# ESP8266.net
KiCad netlist of a schematic drawn in Altium Designer
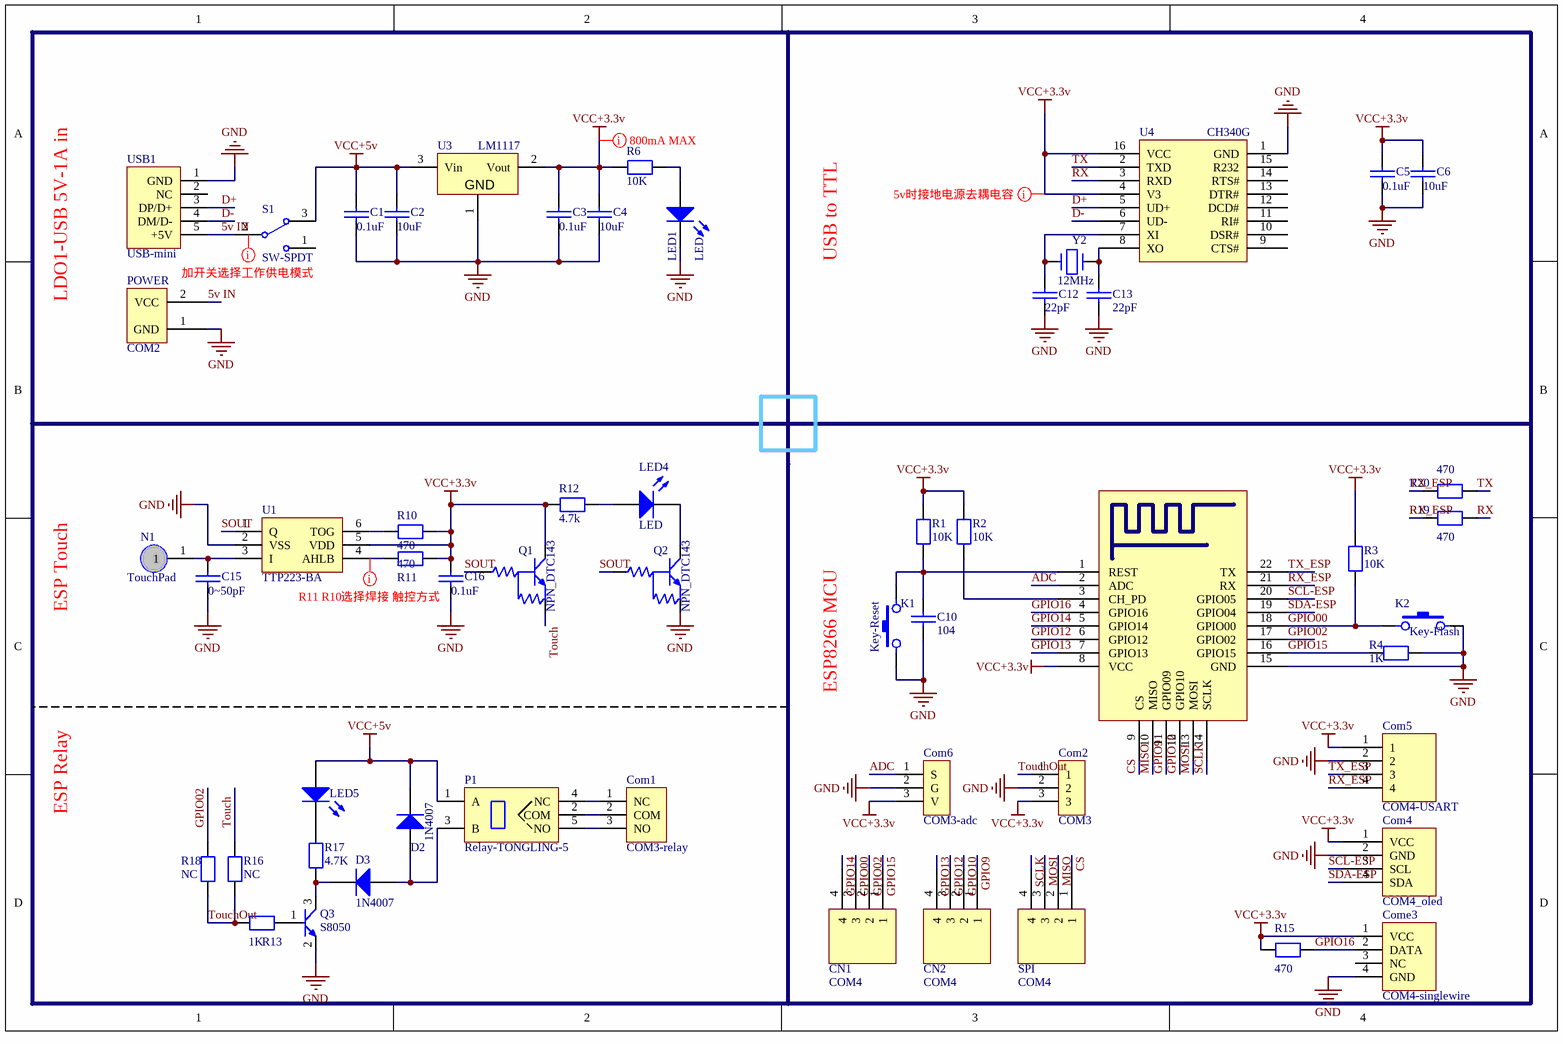
[diagram p0: ESP8266.SchDoc]

(export (version "E")
  (design (tool "Eeschema 10.0.6"))
  (components
    (comp (ref "C1")
      (value "0.1uF")
      (footprint "0603C")
      (description "Capacitor")
      (libsource (lib "myLib") (part "CAP"))
    )
    (comp (ref "C2")
      (value "10uF")
      (footprint "0603C")
      (description "Capacitor")
      (libsource (lib "myLib") (part "CAP"))
    )
    (comp (ref "C3")
      (value "0.1uF")
      (footprint "0603C")
      (description "Capacitor")
      (libsource (lib "myLib") (part "CAP"))
    )
    (comp (ref "C4")
      (value "10uF")
      (footprint "0603C")
      (description "Capacitor")
      (libsource (lib "myLib") (part "CAP"))
    )
    (comp (ref "C5")
      (value "0.1uF")
      (footprint "0603C")
      (description "Capacitor")
      (libsource (lib "myLib") (part "CAP"))
    )
    (comp (ref "C6")
      (value "10uF")
      (footprint "0603C")
      (description "Capacitor")
      (libsource (lib "myLib") (part "CAP"))
    )
    (comp (ref "C10")
      (value "104")
      (footprint "0603C")
      (description "Capacitor")
      (libsource (lib "myLib") (part "CAP"))
    )
    (comp (ref "C12")
      (value "22pF")
      (footprint "0603C")
      (description "Capacitor")
      (libsource (lib "myLib") (part "CAP"))
    )
    (comp (ref "C13")
      (value "22pF")
      (footprint "0603C")
      (description "Capacitor")
      (libsource (lib "myLib") (part "CAP"))
    )
    (comp (ref "C15")
      (value "0~50pF")
      (footprint "0603C")
      (description "Capacitor")
      (libsource (lib "myLib") (part "CAP"))
    )
    (comp (ref "C16")
      (value "0.1uF")
      (footprint "0603C")
      (description "Capacitor")
      (libsource (lib "myLib") (part "CAP"))
    )
    (comp (ref "CN1")
      (value "COM4")
      (footprint "HDR2.54-LI-4P")
      (libsource (lib "altium-import") (part "root_3_COM4_"))
    )
    (comp (ref "CN2")
      (value "COM4")
      (footprint "HDR2.54-LI-4P")
      (libsource (lib "altium-import") (part "root_3_COM4_"))
    )
    (comp (ref "Com1")
      (value "COM3-relay")
      (footprint "KF301-5.0-3P")
      (libsource (lib "myLib") (part "COM3-relay"))
    )
    (comp (ref "Com2") (value "COM3") (footprint "HDR2.54-M-LI-3P") (libsource (lib "myLib") (part "COM3")))
    (comp (ref "Com4")
      (value "COM4_oled")
      (footprint "HDR2.54-4P")
      (libsource (lib "altium-import") (part "root_0_COM4_oled_"))
    )
    (comp (ref "Com5")
      (value "COM4-USART")
      (footprint "HDR2.54-LI-4P")
      (libsource (lib "altium-import") (part "root_0_COM4_"))
    )
    (comp (ref "Com6")
      (value "COM3-adc")
      (footprint "HDR2.54-LI-3P")
      (libsource (lib "myLib") (part "COM3-adc"))
    )
    (comp (ref "Come3")
      (value "COM4-singlewire")
      (footprint "HDR2.54-4P")
      (libsource (lib "myLib") (part "COM4-singlewire"))
    )
    (comp (ref "D2")
      (value "1N4007")
      (footprint "SOD-123")
      (description "High Conductance Fast Diode")
      (fields (field (name "PUBLISHER") "Altium Limited"))
      (libsource (lib "altium-import") (part "root_2_Diode 1N914_"))
    )
    (comp (ref "D3")
      (value "1N4007")
      (footprint "SOD-123")
      (description "High Conductance Fast Diode")
      (fields (field (name "PUBLISHER") "Altium Limited"))
      (libsource (lib "altium-import") (part "root_3_Diode 1N914_"))
    )
    (comp (ref "K1") (value "Key-Reset") (footprint "TSW SMD-3*6*2.5") (libsource (lib "myLib") (part "Key")))
    (comp (ref "K2") (value "Key-Flash") (footprint "TSW SMD-3*6*2.5") (libsource (lib "myLib") (part "Key")))
    (comp (ref "LED1")
      (value "LED")
      (footprint "0603D")
      (description "Typical RED, GREEN, YELLOW, AMBER GaAs LED")
      (fields (field (name "PUBLISHER") "Altium Limited"))
      (libsource (lib "Miscellaneous Devices") (part "LED2"))
    )
    (comp (ref "LED4")
      (value "LED")
      (footprint "0603D")
      (description "Typical RED, GREEN, YELLOW, AMBER GaAs LED")
      (fields (field (name "PUBLISHER") "Altium Limited"))
      (libsource (lib "Miscellaneous Devices") (part "LED2"))
    )
    (comp (ref "LED5")
      (value "LED 0603")
      (footprint "0603D")
      (description "Typical RED, GREEN, YELLOW, AMBER GaAs LED")
      (fields (field (name "PUBLISHER") "Altium Limited"))
      (libsource (lib "Miscellaneous Devices") (part "LED2"))
    )
    (comp (ref "N1") (value "TouchPad") (footprint "TouchPad") (libsource (lib "myLib") (part "TouchPad")))
    (comp (ref "P1")
      (value "Relay-TONGLING-5")
      (footprint "TONGLING-relay-5")
      (libsource (lib "myLib") (part "Relay-TONGLING-5"))
    )
    (comp (ref "POWER") (value "COM2") (footprint "COM2") (libsource (lib "myLib") (part "COM2")))
    (comp (ref "Q1")
      (value "NPN_DTC143")
      (footprint "SOT-523")
      (libsource (lib "altium-import") (part "root_0_NPN_DTC143_"))
    )
    (comp (ref "Q2")
      (value "NPN_DTC143")
      (footprint "SOT-523")
      (libsource (lib "altium-import") (part "root_0_NPN_DTC143_"))
    )
    (comp (ref "Q3")
      (value "S8050")
      (footprint "SOT23")
      (description "NPN Transistor")
      (libsource (lib "myLib") (part "NPN"))
    )
    (comp (ref "R1") (value "10K") (footprint "0603R") (libsource (lib "myLib") (part "RES1")))
    (comp (ref "R2") (value "10K") (footprint "0603R") (libsource (lib "myLib") (part "RES1")))
    (comp (ref "R3") (value "10K") (footprint "0603R") (libsource (lib "myLib") (part "RES1")))
    (comp (ref "R4") (value "1K") (footprint "0603R") (libsource (lib "myLib") (part "RES1")))
    (comp (ref "R6") (value "10K") (footprint "0603R") (libsource (lib "myLib") (part "RES1")))
    (comp (ref "R10") (value "470") (footprint "0603R") (libsource (lib "myLib") (part "RES1")))
    (comp (ref "R11") (value "470") (footprint "0603R") (libsource (lib "myLib") (part "RES1")))
    (comp (ref "R12")
      (value "4.7k")
      (footprint "0603R")
      (libsource (lib "altium-import") (part "root_0_RES1_"))
    )
    (comp (ref "R13") (value "1K") (footprint "0603R") (libsource (lib "myLib") (part "RES1")))
    (comp (ref "R15") (value "470") (footprint "0603R") (libsource (lib "myLib") (part "RES1")))
    (comp (ref "R16") (value "NC") (footprint "0603R") (libsource (lib "myLib") (part "RES1")))
    (comp (ref "R17") (value "4.7K") (footprint "0603R") (libsource (lib "myLib") (part "RES1")))
    (comp (ref "R18") (value "NC") (footprint "0603R") (libsource (lib "myLib") (part "RES1")))
    (comp (ref "R19") (value "470") (footprint "0603R") (libsource (lib "myLib") (part "RES1")))
    (comp (ref "R20") (value "470") (footprint "0603R") (libsource (lib "myLib") (part "RES1")))
    (comp (ref "S1")
      (value "SW-SPDT")
      (footprint "MSK-12C01-07")
      (description "SPDT Subminiature Toggle Switch, Right Angle Mounting, Vertical Actuation")
      (fields (field (name "PUBLISHER") "Altium Limited"))
      (libsource (lib "Miscellaneous Devices") (part "SW-SPDT"))
    )
    (comp (ref "SPI")
      (value "COM4")
      (footprint "HDR2.54-LI-4P")
      (libsource (lib "altium-import") (part "root_3_COM4_"))
    )
    (comp (ref "U1") (value "TTP223-BA") (footprint "SOT23-6") (libsource (lib "myLib") (part "TTP223-BA")))
    (comp (ref "U2") (value "ESP8266") (libsource (lib "myLib") (part "ESP8266")))
    (comp (ref "U3") (value "LM1117") (footprint "SOT223") (libsource (lib "myLib") (part "LM317")))
    (comp (ref "U4") (value "CH340G") (footprint "SOP16") (libsource (lib "myLib") (part "CH340G")))
    (comp (ref "USB1")
      (value "USB-mini")
      (footprint "USB-micro_A")
      (libsource (lib "myLib") (part "USBmini"))
    )
    (comp (ref "Y2")
      (value "12MHz")
      (footprint "YYC 6035-2P")
      (libsource (lib "myLib") (part "CrystalPassive"))
    )
  )
  (nets
    (net (code "1") (name "/5v IN") (class "Default")
      (node (ref "POWER") (pin "2") (pinfunction "VCC_2") (pintype "passive"))
      (node (ref "S1") (pin "2") (pinfunction "2_2") (pintype "passive"))
      (node (ref "USB1") (pin "5") (pinfunction "+5V_5") (pintype "passive"))
    )
    (net (code "2") (name "/ADC") (class "Default")
      (node (ref "Com6") (pin "1") (pinfunction "S_1") (pintype "passive"))
      (node (ref "U2") (pin "2") (pinfunction "ADC_2") (pintype "passive"))
    )
    (net (code "3") (name "/CS") (class "Default")
      (node (ref "SPI") (pin "1") (pinfunction "1_1") (pintype "passive"))
      (node (ref "U2") (pin "9") (pinfunction "CS_9") (pintype "passive"))
    )
    (net (code "4") (name "/D+") (class "Default")
      (node (ref "U4") (pin "5") (pinfunction "UD+_5") (pintype "passive"))
      (node (ref "USB1") (pin "3") (pinfunction "DP/D+_3") (pintype "passive"))
    )
    (net (code "5") (name "/D-") (class "Default")
      (node (ref "U4") (pin "6") (pinfunction "UD-_6") (pintype "passive"))
      (node (ref "USB1") (pin "4") (pinfunction "DM/D-_4") (pintype "passive"))
    )
    (net (code "6") (name "/GPIO00") (class "Default")
      (node (ref "CN1") (pin "3") (pinfunction "3_3") (pintype "passive"))
      (node (ref "K2") (pin "1") (pinfunction "1_1") (pintype "passive"))
      (node (ref "R3") (pin "1") (pinfunction "1_1") (pintype "passive"))
      (node (ref "U2") (pin "18") (pinfunction "GPIO00_18") (pintype "passive"))
    )
    (net (code "7") (name "/GPIO02") (class "Default")
      (node (ref "CN1") (pin "2") (pinfunction "2_2") (pintype "passive"))
      (node (ref "R18") (pin "1") (pinfunction "1_1") (pintype "passive"))
      (node (ref "U2") (pin "17") (pinfunction "GPIO02_17") (pintype "passive"))
    )
    (net (code "8") (name "/GPIO9") (class "Default")
      (node (ref "CN2") (pin "1") (pinfunction "1_1") (pintype "passive"))
      (node (ref "U2") (pin "11") (pinfunction "GPIO09_11") (pintype "passive"))
    )
    (net (code "9") (name "/GPIO10") (class "Default")
      (node (ref "CN2") (pin "2") (pinfunction "2_2") (pintype "passive"))
      (node (ref "U2") (pin "12") (pinfunction "GPIO10_12") (pintype "passive"))
    )
    (net (code "10") (name "/GPIO12") (class "Default")
      (node (ref "CN2") (pin "3") (pinfunction "3_3") (pintype "passive"))
      (node (ref "U2") (pin "6") (pinfunction "GPIO12_6") (pintype "passive"))
    )
    (net (code "11") (name "/GPIO13") (class "Default")
      (node (ref "CN2") (pin "4") (pinfunction "4_4") (pintype "passive"))
      (node (ref "U2") (pin "7") (pinfunction "GPIO13_7") (pintype "passive"))
    )
    (net (code "12") (name "/GPIO14") (class "Default")
      (node (ref "CN1") (pin "4") (pinfunction "4_4") (pintype "passive"))
      (node (ref "U2") (pin "5") (pinfunction "GPIO14_5") (pintype "passive"))
    )
    (net (code "13") (name "/GPIO15") (class "Default")
      (node (ref "CN1") (pin "1") (pinfunction "1_1") (pintype "passive"))
      (node (ref "R4") (pin "2") (pinfunction "2_2") (pintype "passive"))
      (node (ref "U2") (pin "16") (pinfunction "GPIO15_16") (pintype "passive"))
    )
    (net (code "14") (name "/GPIO16") (class "Default")
      (node (ref "Come3") (pin "2") (pinfunction "DATA_2") (pintype "passive"))
      (node (ref "R15") (pin "1") (pinfunction "1_1") (pintype "passive"))
      (node (ref "U2") (pin "4") (pinfunction "GPIO16_4") (pintype "passive"))
    )
    (net (code "15") (name "/MISO") (class "Default")
      (node (ref "SPI") (pin "2") (pinfunction "2_2") (pintype "passive"))
      (node (ref "U2") (pin "10") (pinfunction "MISO_10") (pintype "passive"))
    )
    (net (code "16") (name "/MOSI") (class "Default")
      (node (ref "SPI") (pin "3") (pinfunction "3_3") (pintype "passive"))
      (node (ref "U2") (pin "13") (pinfunction "MOSI_13") (pintype "passive"))
    )
    (net (code "17") (name "/RX") (class "Default")
      (node (ref "R19") (pin "1") (pinfunction "1_1") (pintype "passive"))
      (node (ref "U4") (pin "3") (pinfunction "RXD_3") (pintype "passive"))
    )
    (net (code "18") (name "/RX_ESP") (class "Default")
      (node (ref "Com5") (pin "4") (pinfunction "4_4") (pintype "passive"))
      (node (ref "R19") (pin "2") (pinfunction "2_2") (pintype "passive"))
      (node (ref "U2") (pin "21") (pinfunction "RX_21") (pintype "passive"))
    )
    (net (code "19") (name "/SCL-ESP") (class "Default")
      (node (ref "Com4") (pin "3") (pinfunction "SCL_3") (pintype "passive"))
      (node (ref "U2") (pin "20") (pinfunction "GPIO05_20") (pintype "passive"))
    )
    (net (code "20") (name "/SCLK") (class "Default")
      (node (ref "SPI") (pin "4") (pinfunction "4_4") (pintype "passive"))
      (node (ref "U2") (pin "14") (pinfunction "SCLK_14") (pintype "passive"))
    )
    (net (code "21") (name "/SDA-ESP") (class "Default")
      (node (ref "Com4") (pin "4") (pinfunction "SDA_4") (pintype "passive"))
      (node (ref "U2") (pin "19") (pinfunction "GPIO04_19") (pintype "passive"))
    )
    (net (code "22") (name "/SOUT") (class "Default")
      (node (ref "Q1") (pin "1") (pinfunction "1_1") (pintype "passive"))
      (node (ref "Q2") (pin "1") (pinfunction "1_1") (pintype "passive"))
      (node (ref "U1") (pin "1") (pinfunction "Q_1") (pintype "passive"))
    )
    (net (code "23") (name "/TX") (class "Default")
      (node (ref "R20") (pin "1") (pinfunction "1_1") (pintype "passive"))
      (node (ref "U4") (pin "2") (pinfunction "TXD_2") (pintype "passive"))
    )
    (net (code "24") (name "/TX_ESP") (class "Default")
      (node (ref "Com5") (pin "3") (pinfunction "3_3") (pintype "passive"))
      (node (ref "R20") (pin "2") (pinfunction "2_2") (pintype "passive"))
      (node (ref "U2") (pin "22") (pinfunction "TX_22") (pintype "passive"))
    )
    (net (code "25") (name "/Touch") (class "Default")
      (node (ref "Q1") (pin "2") (pinfunction "2_2") (pintype "passive"))
      (node (ref "R16") (pin "1") (pinfunction "1_1") (pintype "passive"))
    )
    (net (code "26") (name "/TouchOut") (class "Default")
      (node (ref "Com2") (pin "1") (pinfunction "1_1") (pintype "passive"))
      (node (ref "R13") (pin "2") (pinfunction "2_2") (pintype "passive"))
      (node (ref "R16") (pin "2") (pinfunction "2_2") (pintype "passive"))
      (node (ref "R18") (pin "2") (pinfunction "2_2") (pintype "passive"))
    )
    (net (code "27") (name "GND") (class "Default")
      (node (ref "C1") (pin "2") (pinfunction "2_2") (pintype "passive"))
      (node (ref "C10") (pin "2") (pinfunction "2_2") (pintype "passive"))
      (node (ref "C12") (pin "2") (pinfunction "2_2") (pintype "passive"))
      (node (ref "C13") (pin "2") (pinfunction "2_2") (pintype "passive"))
      (node (ref "C15") (pin "2") (pinfunction "2_2") (pintype "passive"))
      (node (ref "C16") (pin "2") (pinfunction "2_2") (pintype "passive"))
      (node (ref "C2") (pin "2") (pinfunction "2_2") (pintype "passive"))
      (node (ref "C3") (pin "2") (pinfunction "2_2") (pintype "passive"))
      (node (ref "C4") (pin "2") (pinfunction "2_2") (pintype "passive"))
      (node (ref "C5") (pin "2") (pinfunction "2_2") (pintype "passive"))
      (node (ref "C6") (pin "2") (pinfunction "2_2") (pintype "passive"))
      (node (ref "Com2") (pin "2") (pinfunction "2_2") (pintype "passive"))
      (node (ref "Com4") (pin "2") (pinfunction "GND_2") (pintype "passive"))
      (node (ref "Com5") (pin "2") (pinfunction "2_2") (pintype "passive"))
      (node (ref "Com6") (pin "2") (pinfunction "G_2") (pintype "passive"))
      (node (ref "Come3") (pin "4") (pinfunction "GND_4") (pintype "passive"))
      (node (ref "K1") (pin "1") (pinfunction "1_1") (pintype "passive"))
      (node (ref "K2") (pin "2") (pinfunction "2_2") (pintype "passive"))
      (node (ref "LED1") (pin "2") (pinfunction "K_2") (pintype "passive"))
      (node (ref "POWER") (pin "1") (pinfunction "GND_1") (pintype "passive"))
      (node (ref "Q2") (pin "2") (pinfunction "2_2") (pintype "passive"))
      (node (ref "Q3") (pin "2") (pinfunction "2_2") (pintype "passive"))
      (node (ref "R4") (pin "1") (pinfunction "1_1") (pintype "passive"))
      (node (ref "U1") (pin "2") (pinfunction "VSS_2") (pintype "passive"))
      (node (ref "U2") (pin "15") (pinfunction "GND_15") (pintype "passive"))
      (node (ref "U3") (pin "1") (pinfunction "ADJ_1") (pintype "passive"))
      (node (ref "U4") (pin "1") (pinfunction "GND_1") (pintype "passive"))
      (node (ref "USB1") (pin "1") (pinfunction "GND_1") (pintype "passive"))
    )
    (net (code "28") (name "Net-(Com1-COM)") (class "Default")
      (node (ref "Com1") (pin "2") (pinfunction "COM_2") (pintype "passive"))
      (node (ref "P1") (pin "2") (pinfunction "COM_2") (pintype "passive"))
    )
    (net (code "29") (name "Net-(Com1-NC)") (class "Default")
      (node (ref "Com1") (pin "1") (pinfunction "NC_1") (pintype "passive"))
      (node (ref "P1") (pin "4") (pinfunction "NC_4") (pintype "passive"))
    )
    (net (code "30") (name "Net-(Com1-NO)") (class "Default")
      (node (ref "Com1") (pin "3") (pinfunction "NO_3") (pintype "passive"))
      (node (ref "P1") (pin "5") (pinfunction "NO_5") (pintype "passive"))
    )
    (net (code "31") (name "Net-(D2-A)") (class "Default")
      (node (ref "D2") (pin "1") (pinfunction "A_1") (pintype "passive"))
      (node (ref "D3") (pin "1") (pinfunction "A_1") (pintype "passive"))
      (node (ref "P1") (pin "3") (pinfunction "B_3") (pintype "passive"))
    )
    (net (code "32") (name "Net-(D3-K)") (class "Default")
      (node (ref "D3") (pin "2") (pinfunction "K_2") (pintype "passive"))
      (node (ref "Q3") (pin "3") (pinfunction "3_3") (pintype "passive"))
      (node (ref "R17") (pin "2") (pinfunction "2_2") (pintype "passive"))
    )
    (net (code "33") (name "Net-(LED1-A)") (class "Default")
      (node (ref "LED1") (pin "1") (pinfunction "A_1") (pintype "passive"))
      (node (ref "R6") (pin "1") (pinfunction "1_1") (pintype "passive"))
    )
    (net (code "34") (name "Net-(LED4-A)") (class "Default")
      (node (ref "LED4") (pin "1") (pinfunction "A_1") (pintype "passive"))
      (node (ref "R12") (pin "2") (pinfunction "2_2") (pintype "passive"))
    )
    (net (code "35") (name "Net-(LED4-K)") (class "Default")
      (node (ref "LED4") (pin "2") (pinfunction "K_2") (pintype "passive"))
      (node (ref "Q2") (pin "3") (pinfunction "3_3") (pintype "passive"))
    )
    (net (code "36") (name "Net-(LED5-K)") (class "Default")
      (node (ref "LED5") (pin "2") (pinfunction "K_2") (pintype "passive"))
      (node (ref "R17") (pin "1") (pinfunction "1_1") (pintype "passive"))
    )
    (net (code "37") (name "Net-(Q3-Pad1)") (class "Default")
      (node (ref "Q3") (pin "1") (pinfunction "1_1") (pintype "passive"))
      (node (ref "R13") (pin "1") (pinfunction "1_1") (pintype "passive"))
    )
    (net (code "38") (name "Net-(U1-AHLB)") (class "Default")
      (node (ref "R11") (pin "2") (pinfunction "2_2") (pintype "passive"))
      (node (ref "U1") (pin "4") (pinfunction "AHLB_4") (pintype "passive"))
    )
    (net (code "39") (name "Net-(U1-I)") (class "Default")
      (node (ref "C15") (pin "1") (pinfunction "1_1") (pintype "passive"))
      (node (ref "N1") (pin "1") (pinfunction "1_1") (pintype "passive"))
      (node (ref "U1") (pin "3") (pinfunction "I_3") (pintype "passive"))
    )
    (net (code "40") (name "Net-(U1-TOG)") (class "Default")
      (node (ref "R10") (pin "2") (pinfunction "2_2") (pintype "passive"))
      (node (ref "U1") (pin "6") (pinfunction "TOG_6") (pintype "passive"))
    )
    (net (code "41") (name "Net-(U2-CH_PD)") (class "Default")
      (node (ref "R2") (pin "1") (pinfunction "1_1") (pintype "passive"))
      (node (ref "U2") (pin "3") (pinfunction "CH_PD_3") (pintype "passive"))
    )
    (net (code "42") (name "Net-(U2-REST)") (class "Default")
      (node (ref "C10") (pin "1") (pinfunction "1_1") (pintype "passive"))
      (node (ref "K1") (pin "2") (pinfunction "2_2") (pintype "passive"))
      (node (ref "R1") (pin "1") (pinfunction "1_1") (pintype "passive"))
      (node (ref "U2") (pin "1") (pinfunction "REST_1") (pintype "passive"))
    )
    (net (code "43") (name "Net-(U4-XI)") (class "Default")
      (node (ref "C12") (pin "1") (pinfunction "1_1") (pintype "passive"))
      (node (ref "U4") (pin "7") (pinfunction "XI_7") (pintype "passive"))
      (node (ref "Y2") (pin "1") (pinfunction "1_1") (pintype "passive"))
    )
    (net (code "44") (name "Net-(U4-XO)") (class "Default")
      (node (ref "C13") (pin "1") (pinfunction "1_1") (pintype "passive"))
      (node (ref "U4") (pin "8") (pinfunction "XO_8") (pintype "passive"))
      (node (ref "Y2") (pin "2") (pinfunction "2_2") (pintype "passive"))
    )
    (net (code "45") (name "VCC+3.3v") (class "Default")
      (node (ref "C16") (pin "1") (pinfunction "1_1") (pintype "passive"))
      (node (ref "C3") (pin "1") (pinfunction "1_1") (pintype "passive"))
      (node (ref "C4") (pin "1") (pinfunction "1_1") (pintype "passive"))
      (node (ref "C5") (pin "1") (pinfunction "1_1") (pintype "passive"))
      (node (ref "C6") (pin "1") (pinfunction "1_1") (pintype "passive"))
      (node (ref "Com2") (pin "3") (pinfunction "3_3") (pintype "passive"))
      (node (ref "Com4") (pin "1") (pinfunction "VCC_1") (pintype "passive"))
      (node (ref "Com5") (pin "1") (pinfunction "1_1") (pintype "passive"))
      (node (ref "Com6") (pin "3") (pinfunction "V_3") (pintype "passive"))
      (node (ref "Come3") (pin "1") (pinfunction "VCC_1") (pintype "passive"))
      (node (ref "Q1") (pin "3") (pinfunction "3_3") (pintype "passive"))
      (node (ref "R1") (pin "2") (pinfunction "2_2") (pintype "passive"))
      (node (ref "R10") (pin "1") (pinfunction "1_1") (pintype "passive"))
      (node (ref "R11") (pin "1") (pinfunction "1_1") (pintype "passive"))
      (node (ref "R12") (pin "1") (pinfunction "1_1") (pintype "passive"))
      (node (ref "R15") (pin "2") (pinfunction "2_2") (pintype "passive"))
      (node (ref "R2") (pin "2") (pinfunction "2_2") (pintype "passive"))
      (node (ref "R3") (pin "2") (pinfunction "2_2") (pintype "passive"))
      (node (ref "R6") (pin "2") (pinfunction "2_2") (pintype "passive"))
      (node (ref "U1") (pin "5") (pinfunction "VDD_5") (pintype "passive"))
      (node (ref "U2") (pin "8") (pinfunction "VCC_8") (pintype "passive"))
      (node (ref "U3") (pin "2") (pinfunction "Vout_2") (pintype "passive"))
      (node (ref "U4") (pin "16") (pinfunction "VCC_16") (pintype "passive"))
      (node (ref "U4") (pin "4") (pinfunction "V3_4") (pintype "passive"))
    )
    (net (code "46") (name "VCC+5v") (class "Default")
      (node (ref "C1") (pin "1") (pinfunction "1_1") (pintype "passive"))
      (node (ref "C2") (pin "1") (pinfunction "1_1") (pintype "passive"))
      (node (ref "D2") (pin "2") (pinfunction "K_2") (pintype "passive"))
      (node (ref "LED5") (pin "1") (pinfunction "A_1") (pintype "passive"))
      (node (ref "P1") (pin "1") (pinfunction "A_1") (pintype "passive"))
      (node (ref "S1") (pin "3") (pinfunction "3_3") (pintype "passive"))
      (node (ref "U3") (pin "3") (pinfunction "Vin_3") (pintype "passive"))
    )
    (net (code "47") (name "unconnected-(Come3-NC-Pad3)") (class "Default")
      (node (ref "Come3") (pin "3") (pinfunction "NC_3") (pintype "passive"))
    )
    (net (code "48") (name "unconnected-(S1-Pad1)") (class "Default")
      (node (ref "S1") (pin "1") (pinfunction "1_1") (pintype "passive"))
    )
    (net (code "49") (name "unconnected-(U4-CTS#-Pad9)") (class "Default")
      (node (ref "U4") (pin "9") (pinfunction "CTS#_9") (pintype "passive"))
    )
    (net (code "50") (name "unconnected-(U4-DCD#-Pad12)") (class "Default")
      (node (ref "U4") (pin "12") (pinfunction "DCD#_12") (pintype "passive"))
    )
    (net (code "51") (name "unconnected-(U4-DSR#-Pad10)") (class "Default")
      (node (ref "U4") (pin "10") (pinfunction "DSR#_10") (pintype "passive"))
    )
    (net (code "52") (name "unconnected-(U4-DTR#-Pad13)") (class "Default")
      (node (ref "U4") (pin "13") (pinfunction "DTR#_13") (pintype "passive"))
    )
    (net (code "53") (name "unconnected-(U4-R232-Pad15)") (class "Default")
      (node (ref "U4") (pin "15") (pinfunction "R232_15") (pintype "passive"))
    )
    (net (code "54") (name "unconnected-(U4-RI#-Pad11)") (class "Default")
      (node (ref "U4") (pin "11") (pinfunction "RI#_11") (pintype "passive"))
    )
    (net (code "55") (name "unconnected-(U4-RTS#-Pad14)") (class "Default")
      (node (ref "U4") (pin "14") (pinfunction "RTS#_14") (pintype "passive"))
    )
    (net (code "56") (name "unconnected-(USB1-NC-Pad2)") (class "Default")
      (node (ref "USB1") (pin "2") (pinfunction "NC_2") (pintype "passive"))
    )
  )
)
